# ZOWI_Main_Board_USB.net
KiCad netlist of a schematic drawn in Altium Designer
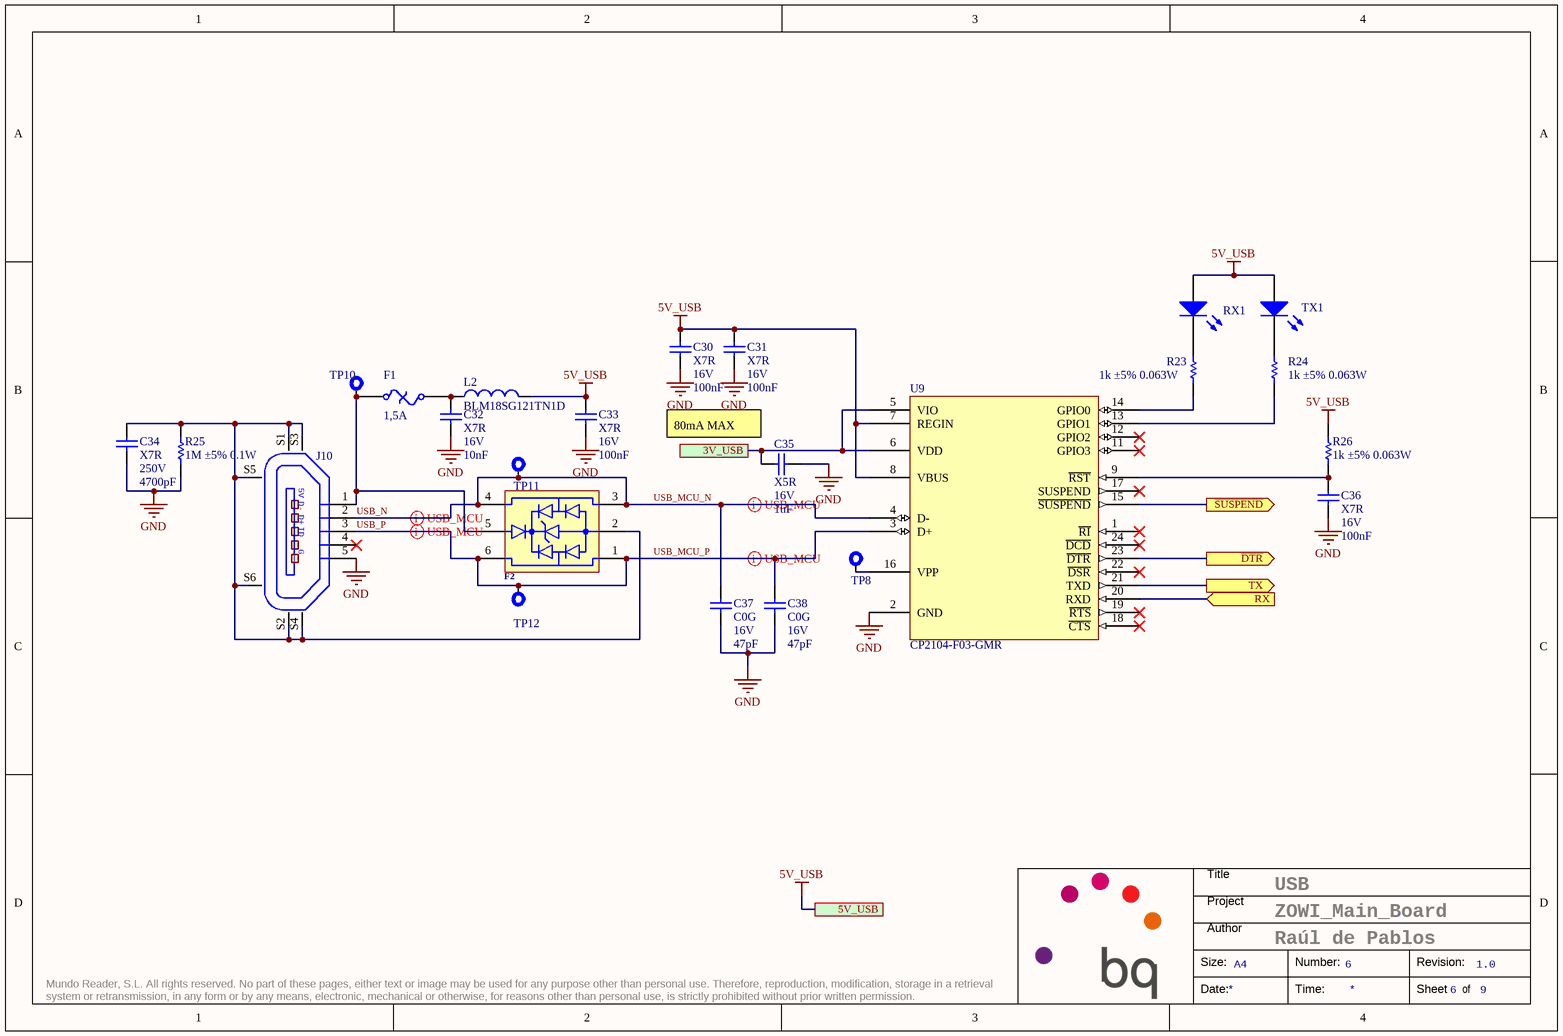
[diagram p0: ZOWI_Main_Board_USB.SchDoc]

(export (version "E")
  (design (tool "Eeschema 10.0.6"))
  (components
    (comp (ref "C30")
      (value "Capacitor")
      (footprint "C0402")
      (description "Capacitor SMD")
      (fields
        (field (name "DIELECTRIC") "X7R")
        (field (name "VOLTAGE") "16V")
        (field (name "CAPACITANCE") "100nF")
        (field (name "PART NUMBER") "C0402_100nF_16V_±10%")
        (field (name "TOLERANCE") "±10%")
      )
      (libsource (lib "Pasives_Capacitor_SMD") (part "Capacitor"))
    )
    (comp (ref "C31")
      (value "Capacitor")
      (footprint "C0402")
      (description "Capacitor SMD")
      (fields
        (field (name "DIELECTRIC") "X7R")
        (field (name "VOLTAGE") "16V")
        (field (name "CAPACITANCE") "100nF")
        (field (name "PART NUMBER") "C0402_100nF_16V_±10%")
        (field (name "TOLERANCE") "±10%")
      )
      (libsource (lib "Pasives_Capacitor_SMD") (part "Capacitor"))
    )
    (comp (ref "C32")
      (value "Capacitor")
      (footprint "C0402")
      (description "Capacitor SMD")
      (fields
        (field (name "DIELECTRIC") "X7R")
        (field (name "VOLTAGE") "16V")
        (field (name "CAPACITANCE") "10nF")
        (field (name "PART NUMBER") "C0402_10nF_16V_±10%")
        (field (name "TOLERANCE") "±10%")
      )
      (libsource (lib "Pasives_Capacitor_SMD") (part "Capacitor"))
    )
    (comp (ref "C33")
      (value "Capacitor")
      (footprint "C0402")
      (description "Capacitor SMD")
      (fields
        (field (name "DIELECTRIC") "X7R")
        (field (name "VOLTAGE") "16V")
        (field (name "CAPACITANCE") "100nF")
        (field (name "PART NUMBER") "C0402_100nF_16V_±10%")
        (field (name "TOLERANCE") "±10%")
      )
      (libsource (lib "Pasives_Capacitor_SMD") (part "Capacitor"))
    )
    (comp (ref "C34")
      (value "Capacitor")
      (footprint "C0805")
      (description "Capacitor SMD")
      (fields
        (field (name "DIELECTRIC") "X7R")
        (field (name "VOLTAGE") "250V")
        (field (name "CAPACITANCE") "4700pF")
        (field (name "PART NUMBER") "C0805_4700pF_250V_±10%")
        (field (name "TOLERANCE") "±10%")
      )
      (libsource (lib "Pasives_Capacitor_SMD") (part "Capacitor"))
    )
    (comp (ref "C35")
      (value "Capacitor")
      (footprint "C0603")
      (description "Capacitor SMD")
      (fields
        (field (name "DIELECTRIC") "X5R")
        (field (name "VOLTAGE") "16V")
        (field (name "CAPACITANCE") "1uF")
        (field (name "PART NUMBER") "C0603_1uF_16V_±10%")
        (field (name "TOLERANCE") "±10%")
      )
      (libsource (lib "Pasives_Capacitor_SMD") (part "Capacitor"))
    )
    (comp (ref "C36")
      (value "Capacitor")
      (footprint "C0402")
      (description "Capacitor SMD")
      (fields
        (field (name "DIELECTRIC") "X7R")
        (field (name "VOLTAGE") "16V")
        (field (name "CAPACITANCE") "100nF")
        (field (name "PART NUMBER") "C0402_100nF_16V_±10%")
        (field (name "TOLERANCE") "±10%")
      )
      (libsource (lib "Pasives_Capacitor_SMD") (part "Capacitor"))
    )
    (comp (ref "C37")
      (value "Capacitor")
      (footprint "C0402")
      (description "Capacitor SMD")
      (fields
        (field (name "DIELECTRIC") "C0G")
        (field (name "VOLTAGE") "16V")
        (field (name "CAPACITANCE") "47pF")
        (field (name "PART NUMBER") "C0402_47pF_16V_±10%")
        (field (name "TOLERANCE") "±10%")
      )
      (libsource (lib "Pasives_Capacitor_SMD") (part "Capacitor"))
    )
    (comp (ref "C38")
      (value "Capacitor")
      (footprint "C0402")
      (description "Capacitor SMD")
      (fields
        (field (name "DIELECTRIC") "C0G")
        (field (name "VOLTAGE") "16V")
        (field (name "CAPACITANCE") "47pF")
        (field (name "PART NUMBER") "C0402_47pF_16V_±10%")
        (field (name "TOLERANCE") "±10%")
      )
      (libsource (lib "Pasives_Capacitor_SMD") (part "Capacitor"))
    )
    (comp (ref "F1")
      (value "PTC_Fuse")
      (footprint "F1812")
      (description "Protection, PTC Resettable Fuse")
      (fields
        (field (name "PART NUMBER") "FUSE 1.5A 24V")
        (field (name "VOLTAGE") "24V")
        (field (name "CURRENT") "1,5A")
      )
      (libsource (lib "Protection") (part "PTC_Fuse"))
    )
    (comp (ref "F2")
      (value "ESDUSB")
      (footprint "SOT563")
      (description "Protection, USB ESD")
      (fields (field (name "PART NUMBER") "USB ESD Single") (field (name "MANUFACTURER") "Würth"))
      (libsource (lib "Protection") (part "ESDUSB"))
    )
    (comp (ref "J10")
      (value "USB_Micro_Type_B")
      (footprint "USB_B_W_REAR_PEGS")
      (description "Connector, USB Micro B")
      (fields
        (field (name "PART NUMBER") "Micro USB Type B W/ Rear Pegs")
        (field (name "MANUFACTURER") "FCI")
      )
      (libsource (lib "Connectors_USB") (part "USB_Micro_Type_B"))
    )
    (comp (ref "L2")
      (value "BLM18SG121TN1D")
      (footprint "L0603")
      (description "Ferrite Bead")
      (fields (field (name "PART NUMBER") "L0603_120R_0,025R_3000mA") (field (name "MANUFACTURER") "Murata"))
      (libsource (lib "Pasivos_Inductor_SMD") (part "Ferrite Bead"))
    )
    (comp (ref "R23")
      (value "1k ±5% 0.063W")
      (footprint "R0402")
      (description "Resistor, SMD")
      (fields (field (name "TOLERANCE") "±5%") (field (name "POWER") "0.063W"))
      (libsource (lib "Pasives_Resistor_SMD") (part "Resistor"))
    )
    (comp (ref "R24")
      (value "1k ±5% 0.063W")
      (footprint "R0402")
      (description "Resistor, SMD")
      (fields (field (name "TOLERANCE") "±5%") (field (name "POWER") "0.063W"))
      (libsource (lib "Pasives_Resistor_SMD") (part "Resistor"))
    )
    (comp (ref "R25")
      (value "1M ±5% 0.1W")
      (footprint "R0603")
      (description "Resistor, SMD")
      (fields (field (name "TOLERANCE") "±5%") (field (name "POWER") "0.1W"))
      (libsource (lib "Pasives_Resistor_SMD") (part "Resistor"))
    )
    (comp (ref "R26")
      (value "1k ±5% 0.063W")
      (footprint "R0402")
      (description "Resistor, SMD")
      (fields (field (name "TOLERANCE") "±5%") (field (name "POWER") "0.063W"))
      (libsource (lib "Pasives_Resistor_SMD") (part "Resistor"))
    )
    (comp (ref "RX1")
      (value "Green")
      (footprint "LED0603")
      (description "LED")
      (fields (field (name "PART NUMBER") "HSMG-C190") (field (name "MANUFACTURER") "Avago Technologies"))
      (libsource (lib "Optoelectronics") (part "LED"))
    )
    (comp (ref "TP8")
      (value "Testpoint")
      (footprint "TP_SMD_1mm")
      (fields (field (name "MANUFACTURER") "Oxley") (field (name "PART NUMBER") "TP_SMD_1mm"))
      (libsource (lib "Miscelanea") (part "Testpoint"))
    )
    (comp (ref "TP10")
      (value "Testpoint")
      (footprint "TP_SMD_1mm")
      (fields (field (name "MANUFACTURER") "Oxley") (field (name "PART NUMBER") "TP_SMD_1mm"))
      (libsource (lib "Miscelanea") (part "Testpoint"))
    )
    (comp (ref "TP11")
      (value "Testpoint")
      (footprint "TP_SMD_1mm")
      (fields (field (name "MANUFACTURER") "Oxley") (field (name "PART NUMBER") "TP_SMD_1mm"))
      (libsource (lib "Miscelanea") (part "Testpoint"))
    )
    (comp (ref "TP12")
      (value "Testpoint")
      (footprint "TP_SMD_1mm")
      (fields (field (name "MANUFACTURER") "Oxley") (field (name "PART NUMBER") "TP_SMD_1mm"))
      (libsource (lib "Miscelanea") (part "Testpoint"))
    )
    (comp (ref "TX1")
      (value "Green")
      (footprint "LED0603")
      (description "LED")
      (fields (field (name "PART NUMBER") "HSMG-C190") (field (name "MANUFACTURER") "Avago Technologies"))
      (libsource (lib "Optoelectronics") (part "LED"))
    )
    (comp (ref "U9")
      (value "CP2104-F03-GMR")
      (footprint "QFN24")
      (description "USB to UART Transceiver")
      (fields
        (field (name "PART NUMBER") "CP2104")
        (field (name "ORDERINGCODE") "CP2104-F03-GMR")
        (field (name "MANUFACTURER") "Silicon Labs")
      )
      (libsource (lib "Transceiver") (part "CP2104"))
    )
  )
  (nets
    (net (code "1") (name "/3V_USB") (class "Default")
      (node (ref "C35") (pin "2") (pinfunction "2_2") (pintype "passive"))
      (node (ref "U9") (pin "5") (pinfunction "VIO_5") (pintype "power_in"))
      (node (ref "U9") (pin "6") (pinfunction "VDD_6") (pintype "power_in"))
    )
    (net (code "2") (name "/RX") (class "Default")
      (node (ref "U9") (pin "20") (pinfunction "RXD_20") (pintype "input"))
    )
    (net (code "3") (name "/TX") (class "Default")
      (node (ref "U9") (pin "21") (pinfunction "TXD_21") (pintype "output"))
    )
    (net (code "4") (name "/USB_MCU_N") (class "Default")
      (node (ref "C37") (pin "2") (pinfunction "2_2") (pintype "passive"))
      (node (ref "F2") (pin "3") (pinfunction "3_3") (pintype "passive"))
      (node (ref "F2") (pin "4") (pinfunction "4_4") (pintype "passive"))
      (node (ref "J10") (pin "2") (pinfunction "P2_2") (pintype "passive"))
      (node (ref "TP11") (pin "1") (pinfunction "1_1") (pintype "passive"))
      (node (ref "U9") (pin "4") (pinfunction "D-_4") (pintype "bidirectional"))
    )
    (net (code "5") (name "/USB_MCU_P") (class "Default")
      (node (ref "C38") (pin "2") (pinfunction "2_2") (pintype "passive"))
      (node (ref "F2") (pin "1") (pinfunction "1_1") (pintype "passive"))
      (node (ref "F2") (pin "6") (pinfunction "6_6") (pintype "passive"))
      (node (ref "J10") (pin "3") (pinfunction "P3_3") (pintype "passive"))
      (node (ref "TP12") (pin "1") (pinfunction "1_1") (pintype "passive"))
      (node (ref "U9") (pin "3") (pinfunction "D+_3") (pintype "bidirectional"))
    )
    (net (code "6") (name "/~{DTR}") (class "Default")
      (node (ref "U9") (pin "23") (pinfunction "~{DTR}_23") (pintype "output"))
    )
    (net (code "7") (name "/~{SUSPEND}") (class "Default")
      (node (ref "U9") (pin "15") (pinfunction "~{SUSPEND}_15") (pintype "output"))
    )
    (net (code "8") (name "5V_USB") (class "Default")
      (node (ref "C30") (pin "2") (pinfunction "2_2") (pintype "passive"))
      (node (ref "C31") (pin "2") (pinfunction "2_2") (pintype "passive"))
      (node (ref "C33") (pin "2") (pinfunction "2_2") (pintype "passive"))
      (node (ref "L2") (pin "2") (pinfunction "2_2") (pintype "passive"))
      (node (ref "R26") (pin "2") (pinfunction "2_2") (pintype "passive"))
      (node (ref "RX1") (pin "A") (pinfunction "A_A") (pintype "passive"))
      (node (ref "TX1") (pin "A") (pinfunction "A_A") (pintype "passive"))
      (node (ref "U9") (pin "7") (pinfunction "REGIN_7") (pintype "power_in"))
      (node (ref "U9") (pin "8") (pinfunction "VBUS_8") (pintype "power_in"))
    )
    (net (code "9") (name "GND") (class "Default")
      (node (ref "C30") (pin "1") (pinfunction "1_1") (pintype "passive"))
      (node (ref "C31") (pin "1") (pinfunction "1_1") (pintype "passive"))
      (node (ref "C32") (pin "1") (pinfunction "1_1") (pintype "passive"))
      (node (ref "C33") (pin "1") (pinfunction "1_1") (pintype "passive"))
      (node (ref "C34") (pin "1") (pinfunction "1_1") (pintype "passive"))
      (node (ref "C35") (pin "1") (pinfunction "1_1") (pintype "passive"))
      (node (ref "C36") (pin "1") (pinfunction "1_1") (pintype "passive"))
      (node (ref "C37") (pin "1") (pinfunction "1_1") (pintype "passive"))
      (node (ref "C38") (pin "1") (pinfunction "1_1") (pintype "passive"))
      (node (ref "J10") (pin "5") (pinfunction "P5_5") (pintype "passive"))
      (node (ref "R25") (pin "1") (pinfunction "1_1") (pintype "passive"))
      (node (ref "U9") (pin "2") (pinfunction "GND_2") (pintype "power_in"))
    )
    (net (code "10") (name "Net-(C32-Pad2)") (class "Default")
      (node (ref "C32") (pin "2") (pinfunction "2_2") (pintype "passive"))
      (node (ref "F1") (pin "2") (pinfunction "2_2") (pintype "passive"))
      (node (ref "L2") (pin "1") (pinfunction "1_1") (pintype "passive"))
    )
    (net (code "11") (name "Net-(J10-P1)") (class "Default")
      (node (ref "F1") (pin "1") (pinfunction "1_1") (pintype "passive"))
      (node (ref "F2") (pin "5") (pinfunction "5_5") (pintype "passive"))
      (node (ref "J10") (pin "1") (pinfunction "P1_1") (pintype "passive"))
      (node (ref "TP10") (pin "1") (pinfunction "1_1") (pintype "passive"))
    )
    (net (code "12") (name "Net-(J10-SHLD1)") (class "Default")
      (node (ref "C34") (pin "2") (pinfunction "2_2") (pintype "passive"))
      (node (ref "F2") (pin "2") (pinfunction "2_2") (pintype "passive"))
      (node (ref "J10") (pin "S1") (pinfunction "SHLD1_S1") (pintype "passive"))
      (node (ref "J10") (pin "S2") (pinfunction "SHLD2_S2") (pintype "passive"))
      (node (ref "J10") (pin "S3") (pinfunction "SHLD3_S3") (pintype "passive"))
      (node (ref "J10") (pin "S4") (pinfunction "SHLD4_S4") (pintype "passive"))
      (node (ref "J10") (pin "S5") (pinfunction "SHLD5_S5") (pintype "passive"))
      (node (ref "J10") (pin "S6") (pinfunction "SHLD6_S6") (pintype "passive"))
      (node (ref "R25") (pin "2") (pinfunction "2_2") (pintype "passive"))
    )
    (net (code "13") (name "Net-(R23-Pad2)") (class "Default")
      (node (ref "R23") (pin "2") (pinfunction "2_2") (pintype "passive"))
      (node (ref "RX1") (pin "K") (pinfunction "K_K") (pintype "passive"))
    )
    (net (code "14") (name "Net-(R24-Pad2)") (class "Default")
      (node (ref "R24") (pin "2") (pinfunction "2_2") (pintype "passive"))
      (node (ref "TX1") (pin "K") (pinfunction "K_K") (pintype "passive"))
    )
    (net (code "15") (name "Net-(U9-GPIO0)") (class "Default")
      (node (ref "R23") (pin "1") (pinfunction "1_1") (pintype "passive"))
      (node (ref "U9") (pin "14") (pinfunction "GPIO0_14") (pintype "bidirectional"))
    )
    (net (code "16") (name "Net-(U9-GPIO1)") (class "Default")
      (node (ref "R24") (pin "1") (pinfunction "1_1") (pintype "passive"))
      (node (ref "U9") (pin "13") (pinfunction "GPIO1_13") (pintype "bidirectional"))
    )
    (net (code "17") (name "Net-(U9-VPP)") (class "Default")
      (node (ref "TP8") (pin "1") (pinfunction "1_1") (pintype "passive"))
      (node (ref "U9") (pin "16") (pinfunction "VPP_16") (pintype "power_in"))
    )
    (net (code "18") (name "Net-(U9-~{RST})") (class "Default")
      (node (ref "C36") (pin "2") (pinfunction "2_2") (pintype "passive"))
      (node (ref "R26") (pin "1") (pinfunction "1_1") (pintype "passive"))
      (node (ref "U9") (pin "9") (pinfunction "~{RST}_9") (pintype "input"))
    )
    (net (code "19") (name "unconnected-(J10-P4-Pad4)") (class "Default")
      (node (ref "J10") (pin "4") (pinfunction "P4_4") (pintype "passive+no_connect"))
    )
    (net (code "20") (name "unconnected-(U9-GPIO2-Pad12)") (class "Default")
      (node (ref "U9") (pin "12") (pinfunction "GPIO2_12") (pintype "bidirectional+no_connect"))
    )
    (net (code "21") (name "unconnected-(U9-GPIO3-Pad11)") (class "Default")
      (node (ref "U9") (pin "11") (pinfunction "GPIO3_11") (pintype "bidirectional+no_connect"))
    )
    (net (code "22") (name "unconnected-(U9-SUSPEND-Pad17)") (class "Default")
      (node (ref "U9") (pin "17") (pinfunction "SUSPEND_17") (pintype "output+no_connect"))
    )
    (net (code "23") (name "unconnected-(U9-~{CTS}-Pad18)") (class "Default")
      (node (ref "U9") (pin "18") (pinfunction "~{CTS}_18") (pintype "input+no_connect"))
    )
    (net (code "24") (name "unconnected-(U9-~{DCD}-Pad24)") (class "Default")
      (node (ref "U9") (pin "24") (pinfunction "~{DCD}_24") (pintype "input+no_connect"))
    )
    (net (code "25") (name "unconnected-(U9-~{DSR}-Pad22)") (class "Default")
      (node (ref "U9") (pin "22") (pinfunction "~{DSR}_22") (pintype "input+no_connect"))
    )
    (net (code "26") (name "unconnected-(U9-~{RI}-Pad1)") (class "Default")
      (node (ref "U9") (pin "1") (pinfunction "~{RI}_1") (pintype "input+no_connect"))
    )
    (net (code "27") (name "unconnected-(U9-~{RTS}-Pad19)") (class "Default")
      (node (ref "U9") (pin "19") (pinfunction "~{RTS}_19") (pintype "output+no_connect"))
    )
  )
)
